# shema.net
KiCad netlist of a schematic drawn in EAGLE
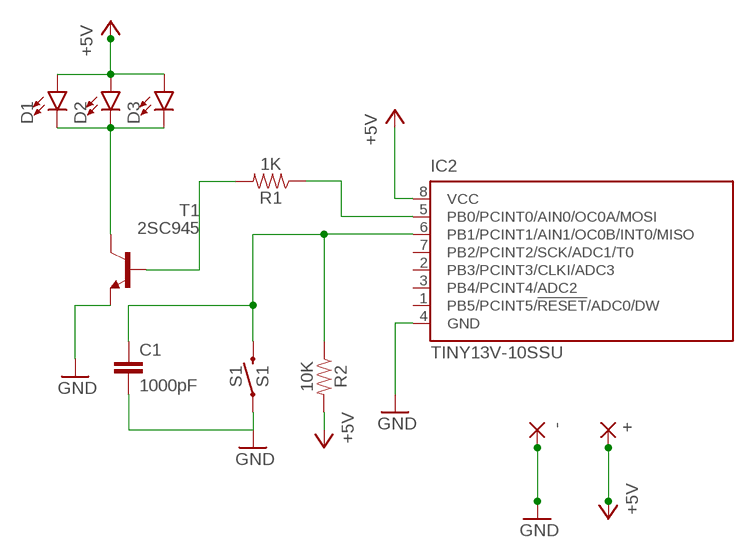
[diagram p0: schematic, sheet 1]

(export (version "E")
  (design (tool "Eeschema 10.0.6"))
  (components
    (comp (ref "+")
      (value "2,54/0,8")
      (footprint "eagle-import:2,54_0,8")
      (libsource (lib "eagle-import") (part "2,54/0,8"))
    )
    (comp (ref "-")
      (value "2,54/0,8")
      (footprint "eagle-import:2,54_0,8")
      (libsource (lib "eagle-import") (part "2,54/0,8"))
    )
    (comp (ref "C1")
      (value "1000pF")
      (footprint "eagle-import:0603")
      (libsource (lib "eagle-import") (part "560PF-0603-50V-5%"))
    )
    (comp (ref "D1")
      (value "LED-3MM-NO_SILK")
      (footprint "eagle-import:LED_3MM-NS")
      (libsource (lib "eagle-import") (part "LED-3MM-NO_SILK"))
    )
    (comp (ref "D2")
      (value "LED-3MM-NO_SILK")
      (footprint "eagle-import:LED_3MM-NS")
      (libsource (lib "eagle-import") (part "LED-3MM-NO_SILK"))
    )
    (comp (ref "D3")
      (value "LED-3MM-NO_SILK")
      (footprint "eagle-import:LED_3MM-NS")
      (libsource (lib "eagle-import") (part "LED-3MM-NO_SILK"))
    )
    (comp (ref "IC2")
      (value "TINY13V-10SSU")
      (footprint "eagle-import:8S1")
      (fields (field (name "MPN") "ATTINY13V-10SSU"))
      (libsource (lib "eagle-import") (part "TINY13SSUV-10"))
    )
    (comp (ref "R1")
      (value "1K")
      (footprint "eagle-import:0603")
      (libsource (lib "eagle-import") (part "2MOHMS-0603-1/10W-1%"))
    )
    (comp (ref "R2")
      (value "10K")
      (footprint "eagle-import:0603")
      (libsource (lib "eagle-import") (part "2MOHMS-0603-1/10W-1%"))
    )
    (comp (ref "S1")
      (value "S1")
      (footprint "eagle-import:TACTILE_SWITCH_SMD_4.5MM")
      (libsource (lib "eagle-import") (part "MOMENTARY-SWITCH-SPST-SMD-4.5MM"))
    )
    (comp (ref "T1")
      (value "2SC945")
      (footprint "eagle-import:TO92-ECB")
      (libsource (lib "eagle-import") (part "2SC945"))
    )
  )
  (nets
    (net (code "1") (name "+5V") (class "Default")
      (node (ref "+") (pin "1") (pinfunction "P_1") (pintype "passive"))
      (node (ref "D1") (pin "A") (pinfunction "A_A") (pintype "passive"))
      (node (ref "D2") (pin "A") (pinfunction "A_A") (pintype "passive"))
      (node (ref "D3") (pin "A") (pinfunction "A_A") (pintype "passive"))
      (node (ref "IC2") (pin "8") (pinfunction "VCC_8") (pintype "power_in"))
      (node (ref "R2") (pin "2") (pinfunction "2_2") (pintype "passive"))
    )
    (net (code "2") (name "GND") (class "Default")
      (node (ref "-") (pin "1") (pinfunction "P_1") (pintype "passive"))
      (node (ref "C1") (pin "2") (pinfunction "2_2") (pintype "passive"))
      (node (ref "IC2") (pin "4") (pinfunction "GND_4") (pintype "power_in"))
      (node (ref "S1") (pin "2") (pinfunction "1_2") (pintype "passive"))
      (node (ref "S1") (pin "3") (pinfunction "1_3") (pintype "passive"))
      (node (ref "T1") (pin "E") (pinfunction "E_E") (pintype "passive"))
    )
    (net (code "3") (name "Net-(D1-C)") (class "Default")
      (node (ref "D1") (pin "K") (pinfunction "C_K") (pintype "passive"))
      (node (ref "D2") (pin "K") (pinfunction "C_K") (pintype "passive"))
      (node (ref "D3") (pin "K") (pinfunction "C_K") (pintype "passive"))
      (node (ref "T1") (pin "C") (pinfunction "C_C") (pintype "passive"))
    )
    (net (code "4") (name "Net-(IC2-PB0{slash}PCINT0{slash}AIN0{slash}OC0A{slash}MOSI)") (class "Default")
      (node (ref "IC2") (pin "5") (pinfunction "PB0/PCINT0/AIN0/OC0A/MOSI_5") (pintype "bidirectional"))
      (node (ref "R1") (pin "1") (pinfunction "1_1") (pintype "passive"))
    )
    (net (code "5") (name "Net-(IC2-PB1{slash}PCINT1{slash}AIN1{slash}OC0B{slash}INT0{slash}MISO)") (class "Default")
      (node (ref "C1") (pin "1") (pinfunction "1_1") (pintype "passive"))
      (node (ref "IC2") (pin "6") (pinfunction "PB1/PCINT1/AIN1/OC0B/INT0/MISO_6") (pintype "bidirectional"))
      (node (ref "R2") (pin "1") (pinfunction "1_1") (pintype "passive"))
      (node (ref "S1") (pin "1") (pinfunction "2_1") (pintype "passive"))
      (node (ref "S1") (pin "4") (pinfunction "2_4") (pintype "passive"))
    )
    (net (code "6") (name "Net-(R1-Pad2)") (class "Default")
      (node (ref "R1") (pin "2") (pinfunction "2_2") (pintype "passive"))
      (node (ref "T1") (pin "B") (pinfunction "B_B") (pintype "passive"))
    )
    (net (code "7") (name "unconnected-(IC2-PB2{slash}PCINT2{slash}SCK{slash}ADC1{slash}T0-Pad7)") (class "Default")
      (node (ref "IC2") (pin "7") (pinfunction "PB2/PCINT2/SCK/ADC1/T0_7") (pintype "bidirectional"))
    )
    (net (code "8") (name "unconnected-(IC2-PB3{slash}PCINT3{slash}CLKI{slash}ADC3-Pad2)") (class "Default")
      (node (ref "IC2") (pin "2") (pinfunction "PB3/PCINT3/CLKI/ADC3_2") (pintype "bidirectional"))
    )
    (net (code "9") (name "unconnected-(IC2-PB4{slash}PCINT4{slash}ADC2-Pad3)") (class "Default")
      (node (ref "IC2") (pin "3") (pinfunction "PB4/PCINT4/ADC2_3") (pintype "bidirectional"))
    )
    (net (code "10") (name "unconnected-(IC2-PB5{slash}PCINT5{slash}~{RESET}{slash}ADC0{slash}DW-Pad1)") (class "Default")
      (node (ref "IC2") (pin "1") (pinfunction "PB5/PCINT5/~{RESET}/ADC0/DW_1") (pintype "bidirectional"))
    )
  )
)
